# Amplifier.net
KiCad netlist of a schematic drawn in Altium Designer
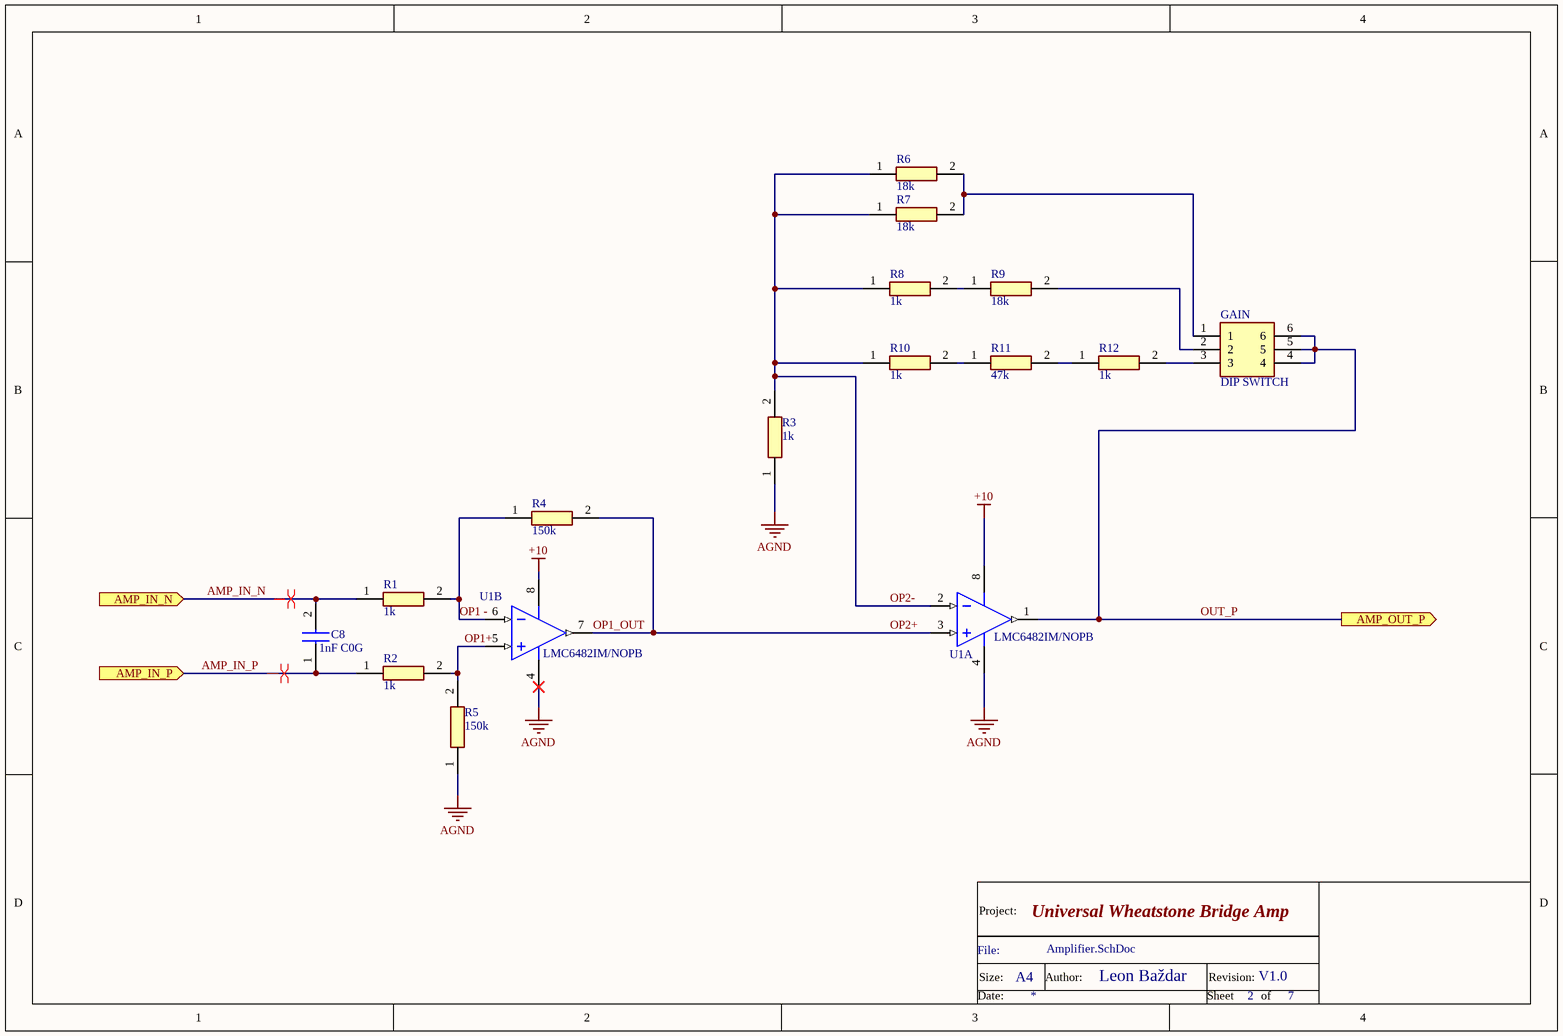
[diagram p0: Amplifier.SchDoc]

(export (version "E")
  (design (tool "Eeschema 10.0.6"))
  (components
    (comp (ref "C8")
      (value "1nF C0G")
      (footprint "SamacSys:CAPC1005X55N")
      (description "Capacitor")
      (fields (field (name "MANUFACTURER_PART_NUMBER") "CGA2B2C0G1H102J050BE"))
      (libsource (lib "*") (part "CGA2B2C0G1H102J050BE"))
    )
    (comp (ref "GAIN")
      (value "DIP SWITCH")
      (footprint "SamacSys:2193LPSTR")
      (description "Switch")
      (fields (field (name "MANUFACTURER_PART_NUMBER") "219-3LPSTR"))
      (libsource (lib "*") (part "219-3LPSTR"))
    )
    (comp (ref "R1")
      (value "1k")
      (footprint "SamacSys:ERA2V_(0402)")
      (description "Resistor")
      (fields (field (name "MANUFACTURER_PART_NUMBER") "ERA-2VEB1001X"))
      (libsource (lib "*") (part "ERA-2VEB1001X"))
    )
    (comp (ref "R2")
      (value "1k")
      (footprint "SamacSys:ERA2V_(0402)")
      (description "Resistor")
      (fields (field (name "MANUFACTURER_PART_NUMBER") "ERA-2VEB1001X"))
      (libsource (lib "*") (part "ERA-2VEB1001X"))
    )
    (comp (ref "R3")
      (value "1k")
      (footprint "SamacSys:ERA2V_(0402)")
      (description "Resistor")
      (fields (field (name "MANUFACTURER_PART_NUMBER") "ERA-2VEB1001X"))
      (libsource (lib "") (part "ERA-2VEB1001X_1"))
    )
    (comp (ref "R4")
      (value "150k")
      (footprint "SamacSys:RESC1005X35N")
      (description "Resistor")
      (fields (field (name "MANUFACTURER_PART_NUMBER") "CPF0402B150KE1"))
      (libsource (lib "") (part "CPF0402B150KE1_1"))
    )
    (comp (ref "R5")
      (value "150k")
      (footprint "SamacSys:RESC1005X35N")
      (description "Resistor")
      (fields (field (name "MANUFACTURER_PART_NUMBER") "CPF0402B150KE1"))
      (libsource (lib "*") (part "CPF0402B150KE1"))
    )
    (comp (ref "R6")
      (value "18k")
      (footprint "SamacSys:RESC1005X35N")
      (description "Resistor")
      (fields (field (name "MANUFACTURER_PART_NUMBER") "CPF0402B18KE1"))
      (libsource (lib "*") (part "CPF0402B18KE1"))
    )
    (comp (ref "R7")
      (value "18k")
      (footprint "SamacSys:RESC1005X35N")
      (description "Resistor")
      (fields (field (name "MANUFACTURER_PART_NUMBER") "CPF0402B18KE1"))
      (libsource (lib "*") (part "CPF0402B18KE1"))
    )
    (comp (ref "R8")
      (value "1k")
      (footprint "SamacSys:ERA2V_(0402)")
      (description "Resistor")
      (fields (field (name "MANUFACTURER_PART_NUMBER") "ERA-2VEB1001X"))
      (libsource (lib "*") (part "ERA-2VEB1001X"))
    )
    (comp (ref "R9")
      (value "18k")
      (footprint "SamacSys:RESC1005X35N")
      (description "Resistor")
      (fields (field (name "MANUFACTURER_PART_NUMBER") "CPF0402B18KE1"))
      (libsource (lib "*") (part "CPF0402B18KE1"))
    )
    (comp (ref "R10")
      (value "1k")
      (footprint "SamacSys:ERA2V_(0402)")
      (description "Resistor")
      (fields (field (name "MANUFACTURER_PART_NUMBER") "ERA-2VEB1001X"))
      (libsource (lib "*") (part "ERA-2VEB1001X"))
    )
    (comp (ref "R11")
      (value "47k")
      (footprint "SamacSys:ERA2A_(0402)")
      (description "Resistor")
      (fields (field (name "MANUFACTURER_PART_NUMBER") "ERA-2APB473X"))
      (libsource (lib "*") (part "ERA-2APB473X"))
    )
    (comp (ref "R12")
      (value "1k")
      (footprint "SamacSys:ERA2V_(0402)")
      (description "Resistor")
      (fields (field (name "MANUFACTURER_PART_NUMBER") "ERA-2VEB1001X"))
      (libsource (lib "*") (part "ERA-2VEB1001X"))
    )
    (comp (ref "U1")
      (value "LMC6482IM/NOPB")
      (footprint "D0008A_N")
      (description "CMOS Dual Rail-to-Rail Input and Output Operational Amplifier, 8-pin Narrow SOIC, Pb-Free")
      (fields (field (name "MANUFACTURER") "Texas Instruments"))
      (libsource (lib "Altium Content Vault") (part "AMP-OPA-LM6132-8"))
    )
  )
  (nets
    (net (code "1") (name "+10") (class "Default")
      (node (ref "U1") (pin "8") (pinfunction "V+_8") (pintype "power_in"))
    )
    (net (code "2") (name "/AMP_IN_N") (class "Default")
      (node (ref "C8") (pin "2") (pinfunction "2_2") (pintype "passive"))
      (node (ref "R1") (pin "1") (pinfunction "1_1") (pintype "passive"))
    )
    (net (code "3") (name "/AMP_IN_P") (class "Default")
      (node (ref "C8") (pin "1") (pinfunction "1_1") (pintype "passive"))
      (node (ref "R2") (pin "1") (pinfunction "1_1") (pintype "passive"))
    )
    (net (code "4") (name "/OP1 -") (class "Default")
      (node (ref "R1") (pin "2") (pinfunction "2_2") (pintype "passive"))
      (node (ref "R4") (pin "1") (pinfunction "1_1") (pintype "passive"))
      (node (ref "U1") (pin "6") (pinfunction "INB-_6") (pintype "input"))
    )
    (net (code "5") (name "/OP1+") (class "Default")
      (node (ref "R2") (pin "2") (pinfunction "2_2") (pintype "passive"))
      (node (ref "R5") (pin "2") (pinfunction "2_2") (pintype "passive"))
      (node (ref "U1") (pin "5") (pinfunction "INB+_5") (pintype "input"))
    )
    (net (code "6") (name "/OP1_OUT") (class "Default")
      (node (ref "R4") (pin "2") (pinfunction "2_2") (pintype "passive"))
      (node (ref "U1") (pin "3") (pinfunction "INA+_3") (pintype "input"))
      (node (ref "U1") (pin "7") (pinfunction "OUTB_7") (pintype "output"))
    )
    (net (code "7") (name "/OP2-") (class "Default")
      (node (ref "R10") (pin "1") (pinfunction "1_1") (pintype "passive"))
      (node (ref "R3") (pin "2") (pinfunction "2_2") (pintype "passive"))
      (node (ref "R6") (pin "1") (pinfunction "1_1") (pintype "passive"))
      (node (ref "R7") (pin "1") (pinfunction "1_1") (pintype "passive"))
      (node (ref "R8") (pin "1") (pinfunction "1_1") (pintype "passive"))
      (node (ref "U1") (pin "2") (pinfunction "INA-_2") (pintype "input"))
    )
    (net (code "8") (name "/OUT_P") (class "Default")
      (node (ref "GAIN") (pin "4") (pinfunction "4_4") (pintype "passive"))
      (node (ref "GAIN") (pin "5") (pinfunction "5_5") (pintype "passive"))
      (node (ref "GAIN") (pin "6") (pinfunction "6_6") (pintype "passive"))
      (node (ref "U1") (pin "1") (pinfunction "OUTA_1") (pintype "output"))
    )
    (net (code "9") (name "AGND") (class "Default")
      (node (ref "R3") (pin "1") (pinfunction "1_1") (pintype "passive"))
      (node (ref "R5") (pin "1") (pinfunction "1_1") (pintype "passive"))
      (node (ref "U1") (pin "4") (pinfunction "V-_4") (pintype "power_in"))
    )
    (net (code "10") (name "Net-(GAIN-Pad1)") (class "Default")
      (node (ref "GAIN") (pin "1") (pinfunction "1_1") (pintype "passive"))
      (node (ref "R6") (pin "2") (pinfunction "2_2") (pintype "passive"))
      (node (ref "R7") (pin "2") (pinfunction "2_2") (pintype "passive"))
    )
    (net (code "11") (name "Net-(GAIN-Pad2)") (class "Default")
      (node (ref "GAIN") (pin "2") (pinfunction "2_2") (pintype "passive"))
      (node (ref "R9") (pin "2") (pinfunction "2_2") (pintype "passive"))
    )
    (net (code "12") (name "Net-(GAIN-Pad3)") (class "Default")
      (node (ref "GAIN") (pin "3") (pinfunction "3_3") (pintype "passive"))
      (node (ref "R12") (pin "2") (pinfunction "2_2") (pintype "passive"))
    )
    (net (code "13") (name "Net-(R8-Pad2)") (class "Default")
      (node (ref "R8") (pin "2") (pinfunction "2_2") (pintype "passive"))
      (node (ref "R9") (pin "1") (pinfunction "1_1") (pintype "passive"))
    )
    (net (code "14") (name "Net-(R10-Pad2)") (class "Default")
      (node (ref "R10") (pin "2") (pinfunction "2_2") (pintype "passive"))
      (node (ref "R11") (pin "1") (pinfunction "1_1") (pintype "passive"))
    )
    (net (code "15") (name "Net-(R11-Pad2)") (class "Default")
      (node (ref "R11") (pin "2") (pinfunction "2_2") (pintype "passive"))
      (node (ref "R12") (pin "1") (pinfunction "1_1") (pintype "passive"))
    )
  )
)
